# robot_base.net
KiCad netlist of a schematic drawn in EAGLE
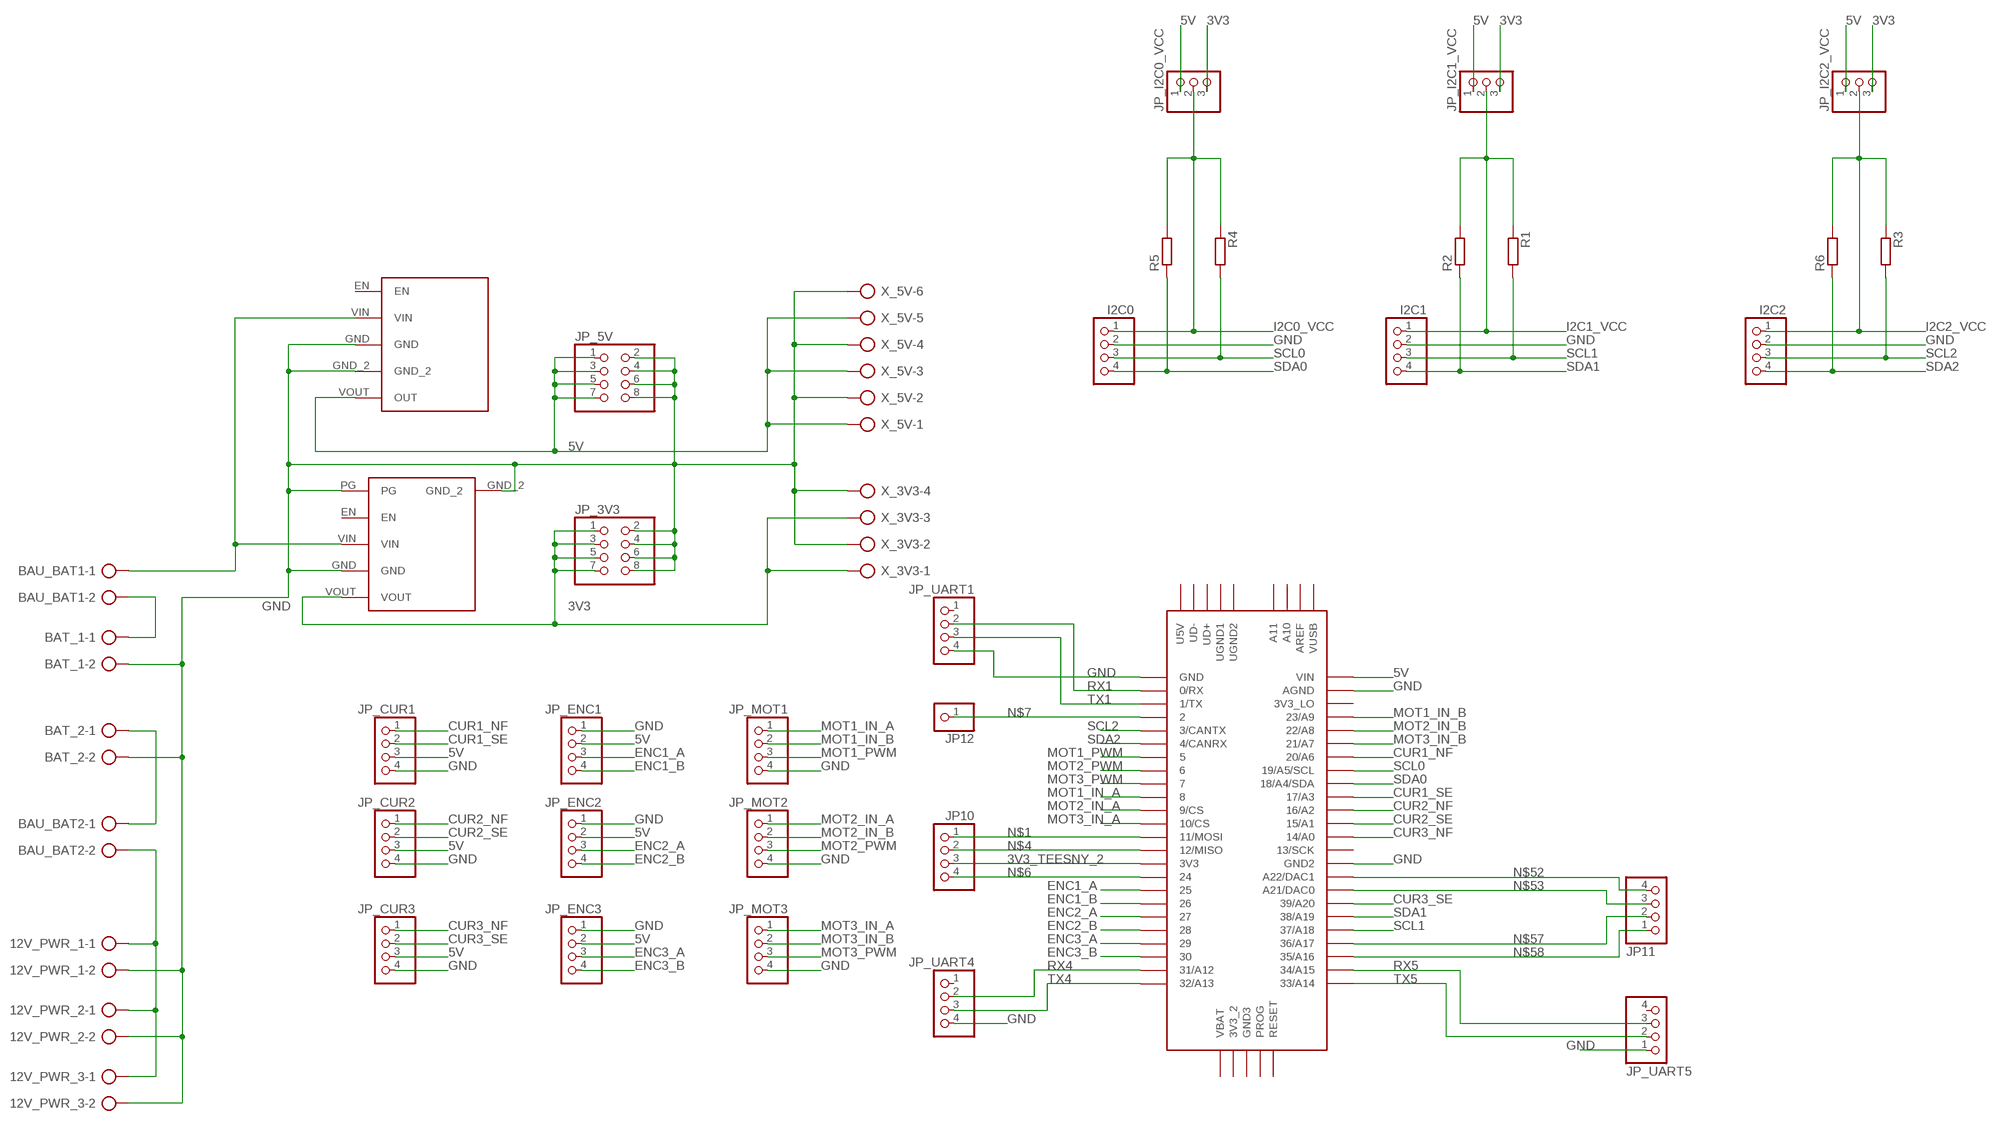
[diagram p0: schematic, sheet 1]

(export (version "E")
  (design (tool "Eeschema 10.0.6"))
  (components
    (comp (ref "12V_PWR_1")
      (value "AK500/2")
      (footprint "eagle-import:AK500_2")
      (libsource (lib "eagle-import") (part "AK500/2"))
    )
    (comp (ref "12V_PWR_2")
      (value "AK500/2")
      (footprint "eagle-import:AK500_2")
      (libsource (lib "eagle-import") (part "AK500/2"))
    )
    (comp (ref "12V_PWR_3")
      (value "AK500/2")
      (footprint "eagle-import:AK500_2")
      (libsource (lib "eagle-import") (part "AK500/2"))
    )
    (comp (ref "BAT_1")
      (value "AK500/2")
      (footprint "eagle-import:AK500_2")
      (libsource (lib "eagle-import") (part "AK500/2"))
    )
    (comp (ref "BAT_2")
      (value "AK500/2")
      (footprint "eagle-import:AK500_2")
      (libsource (lib "eagle-import") (part "AK500/2"))
    )
    (comp (ref "BAU_BAT1")
      (value "AK500/2")
      (footprint "eagle-import:AK500_2")
      (libsource (lib "eagle-import") (part "AK500/2"))
    )
    (comp (ref "BAU_BAT2")
      (value "AK500/2")
      (footprint "eagle-import:AK500_2")
      (libsource (lib "eagle-import") (part "AK500/2"))
    )
    (comp (ref "D24V22F3")
      (value "D24V22F3")
      (footprint "eagle-import:D24V22F3")
      (libsource (lib "eagle-import") (part "D24V22F3"))
    )
    (comp (ref "D24V50F5")
      (value "D24V50F5")
      (footprint "eagle-import:D24V50F5")
      (libsource (lib "eagle-import") (part "D24V50F5"))
    )
    (comp (ref "I2C0")
      (value "PINHD-1X4")
      (footprint "eagle-import:1X04")
      (libsource (lib "eagle-import") (part "PINHD-1X4"))
    )
    (comp (ref "I2C1")
      (value "PINHD-1X4")
      (footprint "eagle-import:1X04")
      (libsource (lib "eagle-import") (part "PINHD-1X4"))
    )
    (comp (ref "I2C2")
      (value "PINHD-1X4")
      (footprint "eagle-import:1X04")
      (libsource (lib "eagle-import") (part "PINHD-1X4"))
    )
    (comp (ref "JP10")
      (value "PINHD-1X4")
      (footprint "eagle-import:1X04")
      (libsource (lib "eagle-import") (part "PINHD-1X4"))
    )
    (comp (ref "JP11")
      (value "PINHD-1X4")
      (footprint "eagle-import:1X04")
      (libsource (lib "eagle-import") (part "PINHD-1X4"))
    )
    (comp (ref "JP12")
      (value "PINHD-1X1")
      (footprint "eagle-import:1X01")
      (libsource (lib "eagle-import") (part "PINHD-1X1"))
    )
    (comp (ref "JP_3V3")
      (value "PINHD-2X4")
      (footprint "eagle-import:2X04")
      (libsource (lib "eagle-import") (part "PINHD-2X4"))
    )
    (comp (ref "JP_5V")
      (value "PINHD-2X4")
      (footprint "eagle-import:2X04")
      (libsource (lib "eagle-import") (part "PINHD-2X4"))
    )
    (comp (ref "JP_CUR1")
      (value "PINHD-1X4")
      (footprint "eagle-import:1X04")
      (libsource (lib "eagle-import") (part "PINHD-1X4"))
    )
    (comp (ref "JP_CUR2")
      (value "PINHD-1X4")
      (footprint "eagle-import:1X04")
      (libsource (lib "eagle-import") (part "PINHD-1X4"))
    )
    (comp (ref "JP_CUR3")
      (value "PINHD-1X4")
      (footprint "eagle-import:1X04")
      (libsource (lib "eagle-import") (part "PINHD-1X4"))
    )
    (comp (ref "JP_ENC1")
      (value "PINHD-1X4")
      (footprint "eagle-import:1X04")
      (libsource (lib "eagle-import") (part "PINHD-1X4"))
    )
    (comp (ref "JP_ENC2")
      (value "PINHD-1X4")
      (footprint "eagle-import:1X04")
      (libsource (lib "eagle-import") (part "PINHD-1X4"))
    )
    (comp (ref "JP_ENC3")
      (value "PINHD-1X4")
      (footprint "eagle-import:1X04")
      (libsource (lib "eagle-import") (part "PINHD-1X4"))
    )
    (comp (ref "JP_I2C0_VCC")
      (value "PINHD-1X3")
      (footprint "eagle-import:1X03")
      (libsource (lib "eagle-import") (part "PINHD-1X3"))
    )
    (comp (ref "JP_I2C1_VCC")
      (value "PINHD-1X3")
      (footprint "eagle-import:1X03")
      (libsource (lib "eagle-import") (part "PINHD-1X3"))
    )
    (comp (ref "JP_I2C2_VCC")
      (value "PINHD-1X3")
      (footprint "eagle-import:1X03")
      (libsource (lib "eagle-import") (part "PINHD-1X3"))
    )
    (comp (ref "JP_MOT1")
      (value "PINHD-1X4")
      (footprint "eagle-import:1X04")
      (libsource (lib "eagle-import") (part "PINHD-1X4"))
    )
    (comp (ref "JP_MOT2")
      (value "PINHD-1X4")
      (footprint "eagle-import:1X04")
      (libsource (lib "eagle-import") (part "PINHD-1X4"))
    )
    (comp (ref "JP_MOT3")
      (value "PINHD-1X4")
      (footprint "eagle-import:1X04")
      (libsource (lib "eagle-import") (part "PINHD-1X4"))
    )
    (comp (ref "JP_UART1")
      (value "PINHD-1X4")
      (footprint "eagle-import:1X04")
      (libsource (lib "eagle-import") (part "PINHD-1X4"))
    )
    (comp (ref "JP_UART4")
      (value "PINHD-1X4")
      (footprint "eagle-import:1X04")
      (libsource (lib "eagle-import") (part "PINHD-1X4"))
    )
    (comp (ref "JP_UART5")
      (value "PINHD-1X4")
      (footprint "eagle-import:1X04")
      (libsource (lib "eagle-import") (part "PINHD-1X4"))
    )
    (comp (ref "R1")
      (value "R-EU_0204/5")
      (footprint "eagle-import:0204_5")
      (libsource (lib "eagle-import") (part "R-EU_0204/5"))
    )
    (comp (ref "R2")
      (value "R-EU_0204/5")
      (footprint "eagle-import:0204_5")
      (libsource (lib "eagle-import") (part "R-EU_0204/5"))
    )
    (comp (ref "R3")
      (value "R-EU_0204/5")
      (footprint "eagle-import:0204_5")
      (libsource (lib "eagle-import") (part "R-EU_0204/5"))
    )
    (comp (ref "R4")
      (value "R-EU_0204/5")
      (footprint "eagle-import:0204_5")
      (libsource (lib "eagle-import") (part "R-EU_0204/5"))
    )
    (comp (ref "R5")
      (value "R-EU_0204/5")
      (footprint "eagle-import:0204_5")
      (libsource (lib "eagle-import") (part "R-EU_0204/5"))
    )
    (comp (ref "R6")
      (value "R-EU_0204/5")
      (footprint "eagle-import:0204_5")
      (libsource (lib "eagle-import") (part "R-EU_0204/5"))
    )
    (comp (ref "U$1")
      (value "TEENSY_3.5/3.6TEENSY_3.5/3.6_LONG_PADS")
      (footprint "eagle-import:TEENSY_3.5_3.6")
      (libsource (lib "eagle-import") (part "TEENSY_3.5/3.6TEENSY_3.5/3.6_LONG_PADS"))
    )
    (comp (ref "X_3V3")
      (value "AK300/4")
      (footprint "eagle-import:AK300_4")
      (libsource (lib "eagle-import") (part "AK300/4"))
    )
    (comp (ref "X_5V")
      (value "AK300/6")
      (footprint "eagle-import:AK300_6")
      (libsource (lib "eagle-import") (part "AK300/6"))
    )
  )
  (nets
    (net (code "1") (name "/3V3") (class "Default")
      (node (ref "D24V22F3") (pin "VOUT") (pinfunction "VOUT_VOUT") (pintype "bidirectional"))
      (node (ref "JP_3V3") (pin "1") (pinfunction "1_1") (pintype "passive"))
      (node (ref "JP_3V3") (pin "3") (pinfunction "3_3") (pintype "passive"))
      (node (ref "JP_3V3") (pin "5") (pinfunction "5_5") (pintype "passive"))
      (node (ref "JP_3V3") (pin "7") (pinfunction "7_7") (pintype "passive"))
      (node (ref "JP_I2C0_VCC") (pin "3") (pinfunction "3_3") (pintype "passive"))
      (node (ref "JP_I2C1_VCC") (pin "3") (pinfunction "3_3") (pintype "passive"))
      (node (ref "JP_I2C2_VCC") (pin "3") (pinfunction "3_3") (pintype "passive"))
      (node (ref "X_3V3") (pin "1") (pinfunction "KL_1") (pintype "passive"))
      (node (ref "X_3V3") (pin "3") (pinfunction "KL_3") (pintype "passive"))
    )
    (net (code "2") (name "/3V3_TEESNY_2") (class "Default")
      (node (ref "JP10") (pin "3") (pinfunction "3_3") (pintype "passive"))
      (node (ref "U$1") (pin "3V3") (pinfunction "3V3_3V3") (pintype "bidirectional"))
    )
    (net (code "3") (name "/5V") (class "Default")
      (node (ref "D24V50F5") (pin "VOUT") (pinfunction "OUT_VOUT") (pintype "bidirectional"))
      (node (ref "JP_5V") (pin "1") (pinfunction "1_1") (pintype "passive"))
      (node (ref "JP_5V") (pin "3") (pinfunction "3_3") (pintype "passive"))
      (node (ref "JP_5V") (pin "5") (pinfunction "5_5") (pintype "passive"))
      (node (ref "JP_5V") (pin "7") (pinfunction "7_7") (pintype "passive"))
      (node (ref "JP_CUR1") (pin "3") (pinfunction "3_3") (pintype "passive"))
      (node (ref "JP_CUR2") (pin "3") (pinfunction "3_3") (pintype "passive"))
      (node (ref "JP_CUR3") (pin "3") (pinfunction "3_3") (pintype "passive"))
      (node (ref "JP_ENC1") (pin "2") (pinfunction "2_2") (pintype "passive"))
      (node (ref "JP_ENC2") (pin "2") (pinfunction "2_2") (pintype "passive"))
      (node (ref "JP_ENC3") (pin "2") (pinfunction "2_2") (pintype "passive"))
      (node (ref "JP_I2C0_VCC") (pin "1") (pinfunction "1_1") (pintype "passive"))
      (node (ref "JP_I2C1_VCC") (pin "1") (pinfunction "1_1") (pintype "passive"))
      (node (ref "JP_I2C2_VCC") (pin "1") (pinfunction "1_1") (pintype "passive"))
      (node (ref "U$1") (pin "VIN") (pinfunction "VIN_VIN") (pintype "bidirectional"))
      (node (ref "X_5V") (pin "1") (pinfunction "KL_1") (pintype "passive"))
      (node (ref "X_5V") (pin "3") (pinfunction "KL_3") (pintype "passive"))
      (node (ref "X_5V") (pin "5") (pinfunction "KL_5") (pintype "passive"))
    )
    (net (code "4") (name "/CUR1_NF") (class "Default")
      (node (ref "JP_CUR1") (pin "1") (pinfunction "1_1") (pintype "passive"))
      (node (ref "U$1") (pin "20/A6") (pinfunction "20/A6_20/A6") (pintype "bidirectional"))
    )
    (net (code "5") (name "/CUR1_SE") (class "Default")
      (node (ref "JP_CUR1") (pin "2") (pinfunction "2_2") (pintype "passive"))
      (node (ref "U$1") (pin "17/A3") (pinfunction "17/A3_17/A3") (pintype "bidirectional"))
    )
    (net (code "6") (name "/CUR2_NF") (class "Default")
      (node (ref "JP_CUR2") (pin "1") (pinfunction "1_1") (pintype "passive"))
      (node (ref "U$1") (pin "16/A2") (pinfunction "16/A2_16/A2") (pintype "bidirectional"))
    )
    (net (code "7") (name "/CUR2_SE") (class "Default")
      (node (ref "JP_CUR2") (pin "2") (pinfunction "2_2") (pintype "passive"))
      (node (ref "U$1") (pin "15/A1") (pinfunction "15/A1_15/A1") (pintype "bidirectional"))
    )
    (net (code "8") (name "/CUR3_NF") (class "Default")
      (node (ref "JP_CUR3") (pin "1") (pinfunction "1_1") (pintype "passive"))
      (node (ref "U$1") (pin "14/A0") (pinfunction "14/A0_14/A0") (pintype "bidirectional"))
    )
    (net (code "9") (name "/CUR3_SE") (class "Default")
      (node (ref "JP_CUR3") (pin "2") (pinfunction "2_2") (pintype "passive"))
      (node (ref "U$1") (pin "39/A20") (pinfunction "39/A20_39/A20") (pintype "bidirectional"))
    )
    (net (code "10") (name "/ENC1_A") (class "Default")
      (node (ref "JP_ENC1") (pin "3") (pinfunction "3_3") (pintype "passive"))
      (node (ref "U$1") (pin "25") (pinfunction "25_25") (pintype "bidirectional"))
    )
    (net (code "11") (name "/ENC1_B") (class "Default")
      (node (ref "JP_ENC1") (pin "4") (pinfunction "4_4") (pintype "passive"))
      (node (ref "U$1") (pin "26") (pinfunction "26_26") (pintype "bidirectional"))
    )
    (net (code "12") (name "/ENC2_A") (class "Default")
      (node (ref "JP_ENC2") (pin "3") (pinfunction "3_3") (pintype "passive"))
      (node (ref "U$1") (pin "27") (pinfunction "27_27") (pintype "bidirectional"))
    )
    (net (code "13") (name "/ENC2_B") (class "Default")
      (node (ref "JP_ENC2") (pin "4") (pinfunction "4_4") (pintype "passive"))
      (node (ref "U$1") (pin "28") (pinfunction "28_28") (pintype "bidirectional"))
    )
    (net (code "14") (name "/ENC3_A") (class "Default")
      (node (ref "JP_ENC3") (pin "3") (pinfunction "3_3") (pintype "passive"))
      (node (ref "U$1") (pin "29") (pinfunction "29_29") (pintype "bidirectional"))
    )
    (net (code "15") (name "/ENC3_B") (class "Default")
      (node (ref "JP_ENC3") (pin "4") (pinfunction "4_4") (pintype "passive"))
      (node (ref "U$1") (pin "30") (pinfunction "30_30") (pintype "bidirectional"))
    )
    (net (code "16") (name "/GND") (class "Default")
      (node (ref "12V_PWR_1") (pin "2") (pinfunction "KL_2") (pintype "passive"))
      (node (ref "12V_PWR_2") (pin "2") (pinfunction "KL_2") (pintype "passive"))
      (node (ref "12V_PWR_3") (pin "2") (pinfunction "KL_2") (pintype "passive"))
      (node (ref "BAT_1") (pin "2") (pinfunction "KL_2") (pintype "passive"))
      (node (ref "BAT_2") (pin "2") (pinfunction "KL_2") (pintype "passive"))
      (node (ref "D24V22F3") (pin "GND") (pinfunction "GND_GND") (pintype "bidirectional"))
      (node (ref "D24V22F3") (pin "GND_2") (pinfunction "GND_2_GND_2") (pintype "bidirectional"))
      (node (ref "D24V22F3") (pin "PG") (pinfunction "PG_PG") (pintype "bidirectional"))
      (node (ref "D24V50F5") (pin "GND") (pinfunction "GND_GND") (pintype "bidirectional"))
      (node (ref "D24V50F5") (pin "GND_2") (pinfunction "GND_2_GND_2") (pintype "bidirectional"))
      (node (ref "I2C0") (pin "2") (pinfunction "2_2") (pintype "passive"))
      (node (ref "I2C1") (pin "2") (pinfunction "2_2") (pintype "passive"))
      (node (ref "I2C2") (pin "2") (pinfunction "2_2") (pintype "passive"))
      (node (ref "JP_3V3") (pin "2") (pinfunction "2_2") (pintype "passive"))
      (node (ref "JP_3V3") (pin "4") (pinfunction "4_4") (pintype "passive"))
      (node (ref "JP_3V3") (pin "6") (pinfunction "6_6") (pintype "passive"))
      (node (ref "JP_3V3") (pin "8") (pinfunction "8_8") (pintype "passive"))
      (node (ref "JP_5V") (pin "2") (pinfunction "2_2") (pintype "passive"))
      (node (ref "JP_5V") (pin "4") (pinfunction "4_4") (pintype "passive"))
      (node (ref "JP_5V") (pin "6") (pinfunction "6_6") (pintype "passive"))
      (node (ref "JP_5V") (pin "8") (pinfunction "8_8") (pintype "passive"))
      (node (ref "JP_CUR1") (pin "4") (pinfunction "4_4") (pintype "passive"))
      (node (ref "JP_CUR2") (pin "4") (pinfunction "4_4") (pintype "passive"))
      (node (ref "JP_CUR3") (pin "4") (pinfunction "4_4") (pintype "passive"))
      (node (ref "JP_ENC1") (pin "1") (pinfunction "1_1") (pintype "passive"))
      (node (ref "JP_ENC2") (pin "1") (pinfunction "1_1") (pintype "passive"))
      (node (ref "JP_ENC3") (pin "1") (pinfunction "1_1") (pintype "passive"))
      (node (ref "JP_MOT1") (pin "4") (pinfunction "4_4") (pintype "passive"))
      (node (ref "JP_MOT2") (pin "4") (pinfunction "4_4") (pintype "passive"))
      (node (ref "JP_MOT3") (pin "4") (pinfunction "4_4") (pintype "passive"))
      (node (ref "JP_UART1") (pin "4") (pinfunction "4_4") (pintype "passive"))
      (node (ref "JP_UART4") (pin "4") (pinfunction "4_4") (pintype "passive"))
      (node (ref "JP_UART5") (pin "1") (pinfunction "1_1") (pintype "passive"))
      (node (ref "U$1") (pin "AGND") (pinfunction "AGND_AGND") (pintype "bidirectional"))
      (node (ref "U$1") (pin "GND") (pinfunction "GND_GND") (pintype "bidirectional"))
      (node (ref "U$1") (pin "GND2") (pinfunction "GND2_GND2") (pintype "bidirectional"))
      (node (ref "X_3V3") (pin "2") (pinfunction "KL_2") (pintype "passive"))
      (node (ref "X_3V3") (pin "4") (pinfunction "KL_4") (pintype "passive"))
      (node (ref "X_5V") (pin "2") (pinfunction "KL_2") (pintype "passive"))
      (node (ref "X_5V") (pin "4") (pinfunction "KL_4") (pintype "passive"))
      (node (ref "X_5V") (pin "6") (pinfunction "KL_6") (pintype "passive"))
    )
    (net (code "17") (name "/I2C0_VCC") (class "Default")
      (node (ref "I2C0") (pin "1") (pinfunction "1_1") (pintype "passive"))
      (node (ref "JP_I2C0_VCC") (pin "2") (pinfunction "2_2") (pintype "passive"))
      (node (ref "R4") (pin "1") (pinfunction "1_1") (pintype "passive"))
      (node (ref "R5") (pin "2") (pinfunction "2_2") (pintype "passive"))
    )
    (net (code "18") (name "/I2C1_VCC") (class "Default")
      (node (ref "I2C1") (pin "1") (pinfunction "1_1") (pintype "passive"))
      (node (ref "JP_I2C1_VCC") (pin "2") (pinfunction "2_2") (pintype "passive"))
      (node (ref "R1") (pin "1") (pinfunction "1_1") (pintype "passive"))
      (node (ref "R2") (pin "2") (pinfunction "2_2") (pintype "passive"))
    )
    (net (code "19") (name "/I2C2_VCC") (class "Default")
      (node (ref "I2C2") (pin "1") (pinfunction "1_1") (pintype "passive"))
      (node (ref "JP_I2C2_VCC") (pin "2") (pinfunction "2_2") (pintype "passive"))
      (node (ref "R3") (pin "1") (pinfunction "1_1") (pintype "passive"))
      (node (ref "R6") (pin "2") (pinfunction "2_2") (pintype "passive"))
    )
    (net (code "20") (name "/MOT1_IN_A") (class "Default")
      (node (ref "JP_MOT1") (pin "1") (pinfunction "1_1") (pintype "passive"))
      (node (ref "U$1") (pin "8") (pinfunction "8_8") (pintype "bidirectional"))
    )
    (net (code "21") (name "/MOT1_IN_B") (class "Default")
      (node (ref "JP_MOT1") (pin "2") (pinfunction "2_2") (pintype "passive"))
      (node (ref "U$1") (pin "23/A9") (pinfunction "23/A9_23/A9") (pintype "bidirectional"))
    )
    (net (code "22") (name "/MOT1_PWM") (class "Default")
      (node (ref "JP_MOT1") (pin "3") (pinfunction "3_3") (pintype "passive"))
      (node (ref "U$1") (pin "5") (pinfunction "5_5") (pintype "bidirectional"))
    )
    (net (code "23") (name "/MOT2_IN_A") (class "Default")
      (node (ref "JP_MOT2") (pin "1") (pinfunction "1_1") (pintype "passive"))
      (node (ref "U$1") (pin "9/CS") (pinfunction "9/CS_9/CS") (pintype "bidirectional"))
    )
    (net (code "24") (name "/MOT2_IN_B") (class "Default")
      (node (ref "JP_MOT2") (pin "2") (pinfunction "2_2") (pintype "passive"))
      (node (ref "U$1") (pin "22/A8") (pinfunction "22/A8_22/A8") (pintype "bidirectional"))
    )
    (net (code "25") (name "/MOT2_PWM") (class "Default")
      (node (ref "JP_MOT2") (pin "3") (pinfunction "3_3") (pintype "passive"))
      (node (ref "U$1") (pin "6") (pinfunction "6_6") (pintype "bidirectional"))
    )
    (net (code "26") (name "/MOT3_IN_A") (class "Default")
      (node (ref "JP_MOT3") (pin "1") (pinfunction "1_1") (pintype "passive"))
      (node (ref "U$1") (pin "10/CS") (pinfunction "10/CS_10/CS") (pintype "bidirectional"))
    )
    (net (code "27") (name "/MOT3_IN_B") (class "Default")
      (node (ref "JP_MOT3") (pin "2") (pinfunction "2_2") (pintype "passive"))
      (node (ref "U$1") (pin "21/A7") (pinfunction "21/A7_21/A7") (pintype "bidirectional"))
    )
    (net (code "28") (name "/MOT3_PWM") (class "Default")
      (node (ref "JP_MOT3") (pin "3") (pinfunction "3_3") (pintype "passive"))
      (node (ref "U$1") (pin "7") (pinfunction "7_7") (pintype "bidirectional"))
    )
    (net (code "29") (name "/N$1") (class "Default")
      (node (ref "JP10") (pin "1") (pinfunction "1_1") (pintype "passive"))
      (node (ref "U$1") (pin "11/MOSI") (pinfunction "11/MOSI_11/MOSI") (pintype "bidirectional"))
    )
    (net (code "30") (name "/N$4") (class "Default")
      (node (ref "JP10") (pin "2") (pinfunction "2_2") (pintype "passive"))
      (node (ref "U$1") (pin "12/MISO") (pinfunction "12/MISO_12/MISO") (pintype "bidirectional"))
    )
    (net (code "31") (name "/N$6") (class "Default")
      (node (ref "JP10") (pin "4") (pinfunction "4_4") (pintype "passive"))
      (node (ref "U$1") (pin "24") (pinfunction "24_24") (pintype "bidirectional"))
    )
    (net (code "32") (name "/N$7") (class "Default")
      (node (ref "JP12") (pin "1") (pinfunction "1_1") (pintype "passive"))
      (node (ref "U$1") (pin "2") (pinfunction "2_2") (pintype "bidirectional"))
    )
    (net (code "33") (name "/N$52") (class "Default")
      (node (ref "JP11") (pin "4") (pinfunction "4_4") (pintype "passive"))
      (node (ref "U$1") (pin "A22/DAC1") (pinfunction "A22/DAC1_A22/DAC1") (pintype "bidirectional"))
    )
    (net (code "34") (name "/N$53") (class "Default")
      (node (ref "JP11") (pin "3") (pinfunction "3_3") (pintype "passive"))
      (node (ref "U$1") (pin "21/DAC0") (pinfunction "A21/DAC0_21/DAC0") (pintype "bidirectional"))
    )
    (net (code "35") (name "/N$57") (class "Default")
      (node (ref "JP11") (pin "2") (pinfunction "2_2") (pintype "passive"))
      (node (ref "U$1") (pin "36/A17") (pinfunction "36/A17_36/A17") (pintype "bidirectional"))
    )
    (net (code "36") (name "/N$58") (class "Default")
      (node (ref "JP11") (pin "1") (pinfunction "1_1") (pintype "passive"))
      (node (ref "U$1") (pin "35/A16") (pinfunction "35/A16_35/A16") (pintype "bidirectional"))
    )
    (net (code "37") (name "/RX1") (class "Default")
      (node (ref "JP_UART1") (pin "2") (pinfunction "2_2") (pintype "passive"))
      (node (ref "U$1") (pin "0/RX") (pinfunction "0/RX_0/RX") (pintype "bidirectional"))
    )
    (net (code "38") (name "/RX4") (class "Default")
      (node (ref "JP_UART4") (pin "2") (pinfunction "2_2") (pintype "passive"))
      (node (ref "U$1") (pin "31/A12") (pinfunction "31/A12_31/A12") (pintype "bidirectional"))
    )
    (net (code "39") (name "/RX5") (class "Default")
      (node (ref "JP_UART5") (pin "3") (pinfunction "3_3") (pintype "passive"))
      (node (ref "U$1") (pin "34/A15") (pinfunction "34/A15_34/A15") (pintype "bidirectional"))
    )
    (net (code "40") (name "/SCL0") (class "Default")
      (node (ref "I2C0") (pin "3") (pinfunction "3_3") (pintype "passive"))
      (node (ref "R4") (pin "2") (pinfunction "2_2") (pintype "passive"))
      (node (ref "U$1") (pin "19/A5/SCL") (pinfunction "19/A5/SCL_19/A5/SCL") (pintype "bidirectional"))
    )
    (net (code "41") (name "/SCL1") (class "Default")
      (node (ref "I2C1") (pin "3") (pinfunction "3_3") (pintype "passive"))
      (node (ref "R1") (pin "2") (pinfunction "2_2") (pintype "passive"))
      (node (ref "U$1") (pin "37/A18") (pinfunction "37/A18_37/A18") (pintype "bidirectional"))
    )
    (net (code "42") (name "/SCL2") (class "Default")
      (node (ref "I2C2") (pin "3") (pinfunction "3_3") (pintype "passive"))
      (node (ref "R3") (pin "2") (pinfunction "2_2") (pintype "passive"))
      (node (ref "U$1") (pin "3/CANTX") (pinfunction "3/CANTX_3/CANTX") (pintype "bidirectional"))
    )
    (net (code "43") (name "/SDA0") (class "Default")
      (node (ref "I2C0") (pin "4") (pinfunction "4_4") (pintype "passive"))
      (node (ref "R5") (pin "1") (pinfunction "1_1") (pintype "passive"))
      (node (ref "U$1") (pin "18/A4/SDA") (pinfunction "18/A4/SDA_18/A4/SDA") (pintype "bidirectional"))
    )
    (net (code "44") (name "/SDA1") (class "Default")
      (node (ref "I2C1") (pin "4") (pinfunction "4_4") (pintype "passive"))
      (node (ref "R2") (pin "1") (pinfunction "1_1") (pintype "passive"))
      (node (ref "U$1") (pin "38/A19") (pinfunction "38/A19_38/A19") (pintype "bidirectional"))
    )
    (net (code "45") (name "/SDA2") (class "Default")
      (node (ref "I2C2") (pin "4") (pinfunction "4_4") (pintype "passive"))
      (node (ref "R6") (pin "1") (pinfunction "1_1") (pintype "passive"))
      (node (ref "U$1") (pin "4/CANRX") (pinfunction "4/CANRX_4/CANRX") (pintype "bidirectional"))
    )
    (net (code "46") (name "/TX1") (class "Default")
      (node (ref "JP_UART1") (pin "3") (pinfunction "3_3") (pintype "passive"))
      (node (ref "U$1") (pin "1/TX") (pinfunction "1/TX_1/TX") (pintype "bidirectional"))
    )
    (net (code "47") (name "/TX4") (class "Default")
      (node (ref "JP_UART4") (pin "3") (pinfunction "3_3") (pintype "passive"))
      (node (ref "U$1") (pin "32/A13") (pinfunction "32/A13_32/A13") (pintype "bidirectional"))
    )
    (net (code "48") (name "/TX5") (class "Default")
      (node (ref "JP_UART5") (pin "2") (pinfunction "2_2") (pintype "passive"))
      (node (ref "U$1") (pin "33/A14") (pinfunction "33/A14_33/A14") (pintype "bidirectional"))
    )
    (net (code "49") (name "Net-(12V_PWR_1A-KL)") (class "Default")
      (node (ref "12V_PWR_1") (pin "1") (pinfunction "KL_1") (pintype "passive"))
      (node (ref "12V_PWR_2") (pin "1") (pinfunction "KL_1") (pintype "passive"))
      (node (ref "12V_PWR_3") (pin "1") (pinfunction "KL_1") (pintype "passive"))
      (node (ref "BAU_BAT2") (pin "2") (pinfunction "KL_2") (pintype "passive"))
    )
    (net (code "50") (name "Net-(BAT_1A-KL)") (class "Default")
      (node (ref "BAT_1") (pin "1") (pinfunction "KL_1") (pintype "passive"))
      (node (ref "BAU_BAT1") (pin "2") (pinfunction "KL_2") (pintype "passive"))
    )
    (net (code "51") (name "Net-(BAT_2A-KL)") (class "Default")
      (node (ref "BAT_2") (pin "1") (pinfunction "KL_1") (pintype "passive"))
      (node (ref "BAU_BAT2") (pin "1") (pinfunction "KL_1") (pintype "passive"))
    )
    (net (code "52") (name "Net-(BAU_BAT1A-KL)") (class "Default")
      (node (ref "BAU_BAT1") (pin "1") (pinfunction "KL_1") (pintype "passive"))
      (node (ref "D24V22F3") (pin "VIN") (pinfunction "VIN_VIN") (pintype "bidirectional"))
      (node (ref "D24V50F5") (pin "VIN") (pinfunction "VIN_VIN") (pintype "bidirectional"))
    )
    (net (code "53") (name "unconnected-(D24V22F3-PadEN)") (class "Default")
      (node (ref "D24V22F3") (pin "EN") (pinfunction "EN_EN") (pintype "bidirectional"))
    )
    (net (code "54") (name "unconnected-(D24V50F5-PadEN)") (class "Default")
      (node (ref "D24V50F5") (pin "EN") (pinfunction "EN_EN") (pintype "bidirectional"))
    )
    (net (code "55") (name "unconnected-(JP_UART1-Pad1)") (class "Default")
      (node (ref "JP_UART1") (pin "1") (pinfunction "1_1") (pintype "passive"))
    )
    (net (code "56") (name "unconnected-(JP_UART4-Pad1)") (class "Default")
      (node (ref "JP_UART4") (pin "1") (pinfunction "1_1") (pintype "passive"))
    )
    (net (code "57") (name "unconnected-(JP_UART5-Pad4)") (class "Default")
      (node (ref "JP_UART5") (pin "4") (pinfunction "4_4") (pintype "passive"))
    )
    (net (code "58") (name "unconnected-(U$1-Pad3V3_2)") (class "Default")
      (node (ref "U$1") (pin "3V3_2") (pinfunction "3V3_2_3V3_2") (pintype "bidirectional"))
    )
    (net (code "59") (name "unconnected-(U$1-Pad3V3_LO)") (class "Default")
      (node (ref "U$1") (pin "3V3_LO") (pinfunction "3V3_LO_3V3_LO") (pintype "bidirectional"))
    )
    (net (code "60") (name "unconnected-(U$1-Pad13{slash}SCK)") (class "Default")
      (node (ref "U$1") (pin "13/SCK") (pinfunction "13/SCK_13/SCK") (pintype "bidirectional"))
    )
    (net (code "61") (name "unconnected-(U$1-PadA10)") (class "Default")
      (node (ref "U$1") (pin "A10") (pinfunction "A10_A10") (pintype "bidirectional"))
    )
    (net (code "62") (name "unconnected-(U$1-PadA11)") (class "Default")
      (node (ref "U$1") (pin "A11") (pinfunction "A11_A11") (pintype "bidirectional"))
    )
    (net (code "63") (name "unconnected-(U$1-PadAREF)") (class "Default")
      (node (ref "U$1") (pin "AREF") (pinfunction "AREF_AREF") (pintype "bidirectional"))
    )
    (net (code "64") (name "unconnected-(U$1-PadGND3)") (class "Default")
      (node (ref "U$1") (pin "GND3") (pinfunction "GND3_GND3") (pintype "bidirectional"))
    )
    (net (code "65") (name "unconnected-(U$1-PadPROG)") (class "Default")
      (node (ref "U$1") (pin "PROG") (pinfunction "PROG_PROG") (pintype "bidirectional"))
    )
    (net (code "66") (name "unconnected-(U$1-PadRESET)") (class "Default")
      (node (ref "U$1") (pin "RESET") (pinfunction "RESET_RESET") (pintype "bidirectional"))
    )
    (net (code "67") (name "unconnected-(U$1-PadU5V)") (class "Default")
      (node (ref "U$1") (pin "U5V") (pinfunction "U5V_U5V") (pintype "bidirectional"))
    )
    (net (code "68") (name "unconnected-(U$1-PadUD+)") (class "Default")
      (node (ref "U$1") (pin "UD+") (pinfunction "UD+_UD+") (pintype "bidirectional"))
    )
    (net (code "69") (name "unconnected-(U$1-PadUD-)") (class "Default")
      (node (ref "U$1") (pin "UD-") (pinfunction "UD-_UD-") (pintype "bidirectional"))
    )
    (net (code "70") (name "unconnected-(U$1-PadUGND1)") (class "Default")
      (node (ref "U$1") (pin "UGND1") (pinfunction "UGND1_UGND1") (pintype "bidirectional"))
    )
    (net (code "71") (name "unconnected-(U$1-PadUGND2)") (class "Default")
      (node (ref "U$1") (pin "UGND2") (pinfunction "UGND2_UGND2") (pintype "bidirectional"))
    )
    (net (code "72") (name "unconnected-(U$1-PadVBAT)") (class "Default")
      (node (ref "U$1") (pin "VBAT") (pinfunction "VBAT_VBAT") (pintype "bidirectional"))
    )
    (net (code "73") (name "unconnected-(U$1-PadVUSB)") (class "Default")
      (node (ref "U$1") (pin "VUSB") (pinfunction "VUSB_VUSB") (pintype "bidirectional"))
    )
  )
)
